# Bank1_I_O.net
KiCad netlist of a schematic drawn in Altium Designer
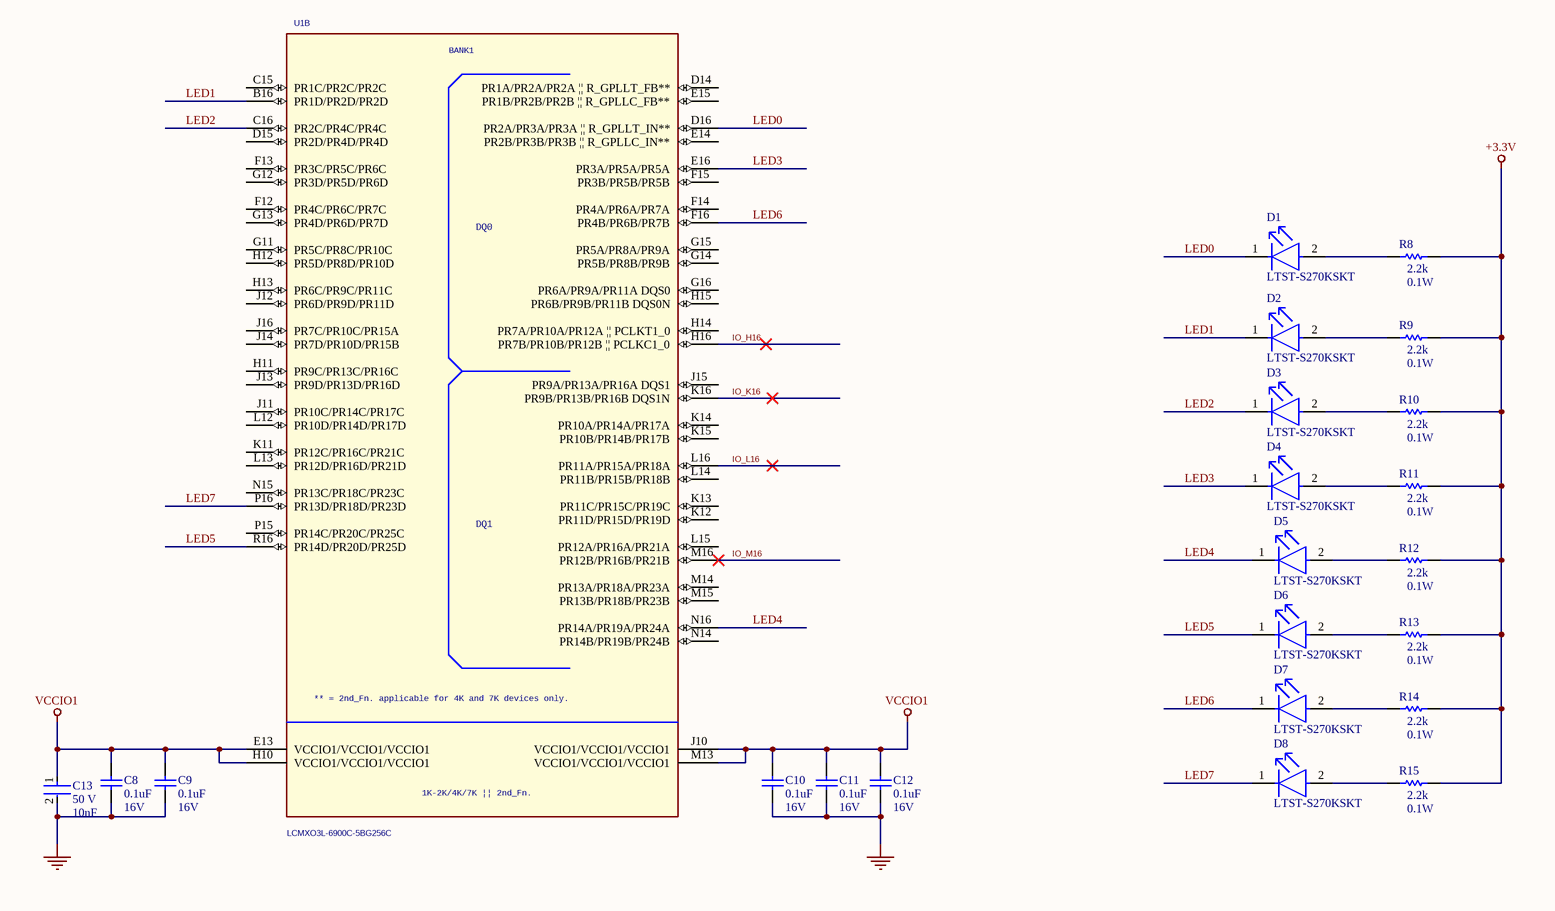
[diagram p0: Bank1_I_O.SchDoc]

(export (version "E")
  (design (tool "Eeschema 10.0.6"))
  (components
    (comp (ref "C8")
      (value "0.1uF")
      (footprint "CAPC1608X87X35ML15T15")
      (description "Ceramic Capacitor 0.1uF 16V +-10% X7R0603")
      (fields
        (field (name "PART NUMBER") "C0603C104M4RACTU")
        (field (name "MANUFACTURER") "Kemet")
        (field (name "VOLTAGE") "16V")
      )
      (libsource (lib "Altium Content Vault") (part "CAP"))
    )
    (comp (ref "C9")
      (value "0.1uF")
      (footprint "CAPC1608X87X35ML15T15")
      (description "Ceramic Capacitor 0.1uF 16V +-10% X7R0603")
      (fields
        (field (name "PART NUMBER") "C0603C104M4RACTU")
        (field (name "MANUFACTURER") "Kemet")
        (field (name "VOLTAGE") "16V")
      )
      (libsource (lib "Altium Content Vault") (part "CAP"))
    )
    (comp (ref "C10")
      (value "0.1uF")
      (footprint "CAPC1608X87X35ML15T15")
      (description "Ceramic Capacitor 0.1uF 16V +-10% X7R0603")
      (fields
        (field (name "PART NUMBER") "C0603C104M4RACTU")
        (field (name "MANUFACTURER") "Kemet")
        (field (name "VOLTAGE") "16V")
      )
      (libsource (lib "Altium Content Vault") (part "CAP"))
    )
    (comp (ref "C11")
      (value "0.1uF")
      (footprint "CAPC1608X87X35ML15T15")
      (description "Ceramic Capacitor 0.1uF 16V +-10% X7R0603")
      (fields
        (field (name "PART NUMBER") "C0603C104M4RACTU")
        (field (name "MANUFACTURER") "Kemet")
        (field (name "VOLTAGE") "16V")
      )
      (libsource (lib "Altium Content Vault") (part "CAP"))
    )
    (comp (ref "C12")
      (value "0.1uF")
      (footprint "CAPC1608X87X35ML15T15")
      (description "Ceramic Capacitor 0.1uF 16V +-10% X7R0603")
      (fields
        (field (name "PART NUMBER") "C0603C104M4RACTU")
        (field (name "MANUFACTURER") "Kemet")
        (field (name "VOLTAGE") "16V")
      )
      (libsource (lib "Altium Content Vault") (part "CAP"))
    )
    (comp (ref "C13")
      (value "10nF")
      (footprint "FP-C0805C-DN-MFG")
      (description "CAP CER 10000PF 50V X7R 0805")
      (fields
        (field (name "VOLTAGE") "50 V")
        (field (name "PART NUMBER") "C0805C103K5RACAUTO")
        (field (name "MANUFACTURER") "KEMET")
      )
      (libsource (lib "Altium Content Vault") (part "b4654b650e69147ec39a6b967a45e02"))
    )
    (comp (ref "D1")
      (value "LTST-S270KSKT")
      (footprint "FP-LTST-S270KSKT-MFG")
      (description "LED YELLOW CLEAR CHIP SMD R/A")
      (libsource (lib "Altium Content Vault") (part "8706943c75ba83719d021d2fdc84c58"))
    )
    (comp (ref "D2")
      (value "LTST-S270KSKT")
      (footprint "FP-LTST-S270KSKT-MFG")
      (description "LED YELLOW CLEAR CHIP SMD R/A")
      (libsource (lib "Altium Content Vault") (part "8706943c75ba83719d021d2fdc84c58"))
    )
    (comp (ref "D3")
      (value "LTST-S270KSKT")
      (footprint "FP-LTST-S270KSKT-MFG")
      (description "LED YELLOW CLEAR CHIP SMD R/A")
      (libsource (lib "Altium Content Vault") (part "8706943c75ba83719d021d2fdc84c58"))
    )
    (comp (ref "D4")
      (value "LTST-S270KSKT")
      (footprint "FP-LTST-S270KSKT-MFG")
      (description "LED YELLOW CLEAR CHIP SMD R/A")
      (libsource (lib "Altium Content Vault") (part "8706943c75ba83719d021d2fdc84c58"))
    )
    (comp (ref "D5")
      (value "LTST-S270KSKT")
      (footprint "FP-LTST-S270KSKT-MFG")
      (description "LED YELLOW CLEAR CHIP SMD R/A")
      (libsource (lib "Altium Content Vault") (part "8706943c75ba83719d021d2fdc84c58"))
    )
    (comp (ref "D6")
      (value "LTST-S270KSKT")
      (footprint "FP-LTST-S270KSKT-MFG")
      (description "LED YELLOW CLEAR CHIP SMD R/A")
      (libsource (lib "Altium Content Vault") (part "8706943c75ba83719d021d2fdc84c58"))
    )
    (comp (ref "D7")
      (value "LTST-S270KSKT")
      (footprint "FP-LTST-S270KSKT-MFG")
      (description "LED YELLOW CLEAR CHIP SMD R/A")
      (libsource (lib "Altium Content Vault") (part "8706943c75ba83719d021d2fdc84c58"))
    )
    (comp (ref "D8")
      (value "LTST-S270KSKT")
      (footprint "FP-LTST-S270KSKT-MFG")
      (description "LED YELLOW CLEAR CHIP SMD R/A")
      (libsource (lib "Altium Content Vault") (part "8706943c75ba83719d021d2fdc84c58"))
    )
    (comp (ref "R8")
      (value "2.2k")
      (footprint "RESC1608X55X25LL10T15")
      (fields
        (field (name "TOLERANCE") "1%")
        (field (name "VOLTAGE") "50V")
        (field (name "MANUFACTURER") "Yageo")
        (field (name "POWER") "0.1W")
      )
      (libsource (lib "Altium Content Vault") (part "RES-2"))
    )
    (comp (ref "R9")
      (value "2.2k")
      (footprint "RESC1608X55X25LL10T15")
      (fields
        (field (name "TOLERANCE") "1%")
        (field (name "VOLTAGE") "50V")
        (field (name "MANUFACTURER") "Yageo")
        (field (name "POWER") "0.1W")
      )
      (libsource (lib "Altium Content Vault") (part "RES-2"))
    )
    (comp (ref "R10")
      (value "2.2k")
      (footprint "RESC1608X55X25LL10T15")
      (fields
        (field (name "TOLERANCE") "1%")
        (field (name "VOLTAGE") "50V")
        (field (name "MANUFACTURER") "Yageo")
        (field (name "POWER") "0.1W")
      )
      (libsource (lib "Altium Content Vault") (part "RES-2"))
    )
    (comp (ref "R11")
      (value "2.2k")
      (footprint "RESC1608X55X25LL10T15")
      (fields
        (field (name "TOLERANCE") "1%")
        (field (name "VOLTAGE") "50V")
        (field (name "MANUFACTURER") "Yageo")
        (field (name "POWER") "0.1W")
      )
      (libsource (lib "Altium Content Vault") (part "RES-2"))
    )
    (comp (ref "R12")
      (value "2.2k")
      (footprint "RESC1608X55X25LL10T15")
      (fields
        (field (name "TOLERANCE") "1%")
        (field (name "VOLTAGE") "50V")
        (field (name "MANUFACTURER") "Yageo")
        (field (name "POWER") "0.1W")
      )
      (libsource (lib "Altium Content Vault") (part "RES-2"))
    )
    (comp (ref "R13")
      (value "2.2k")
      (footprint "RESC1608X55X25LL10T15")
      (fields
        (field (name "TOLERANCE") "1%")
        (field (name "VOLTAGE") "50V")
        (field (name "MANUFACTURER") "Yageo")
        (field (name "POWER") "0.1W")
      )
      (libsource (lib "Altium Content Vault") (part "RES-2"))
    )
    (comp (ref "R14")
      (value "2.2k")
      (footprint "RESC1608X55X25LL10T15")
      (fields
        (field (name "TOLERANCE") "1%")
        (field (name "VOLTAGE") "50V")
        (field (name "MANUFACTURER") "Yageo")
        (field (name "POWER") "0.1W")
      )
      (libsource (lib "Altium Content Vault") (part "RES-2"))
    )
    (comp (ref "R15")
      (value "2.2k")
      (footprint "RESC1608X55X25LL10T15")
      (fields
        (field (name "TOLERANCE") "1%")
        (field (name "VOLTAGE") "50V")
        (field (name "MANUFACTURER") "Yageo")
        (field (name "POWER") "0.1W")
      )
      (libsource (lib "Altium Content Vault") (part "RES-2"))
    )
    (comp (ref "U1")
      (value "LCMXO3L-6900C-5BG256C")
      (footprint "BGA256C80P16X16_1400X1400X170")
      (description "IC FPGA 6864LUTS 256BGA")
      (fields (field (name "MANUFACTURER") "Lattice semi"))
      (libsource (lib "*") (part "LCMXO3L-1K/2K/4K/7K-BG256"))
    )
  )
  (nets
    (net (code "1") (name "+3.3V") (class "Default")
      (node (ref "R10") (pin "2") (pinfunction "2_2") (pintype "passive"))
      (node (ref "R11") (pin "2") (pinfunction "2_2") (pintype "passive"))
      (node (ref "R12") (pin "2") (pinfunction "2_2") (pintype "passive"))
      (node (ref "R13") (pin "2") (pinfunction "2_2") (pintype "passive"))
      (node (ref "R14") (pin "2") (pinfunction "2_2") (pintype "passive"))
      (node (ref "R15") (pin "2") (pinfunction "2_2") (pintype "passive"))
      (node (ref "R8") (pin "2") (pinfunction "2_2") (pintype "passive"))
      (node (ref "R9") (pin "2") (pinfunction "2_2") (pintype "passive"))
    )
    (net (code "2") (name "/IO_H16") (class "Default")
      (node (ref "U1") (pin "H16") (pinfunction "PR7B/PR10B/PR12B_Ζ_PCLKC1_0_H16") (pintype "bidirectional"))
    )
    (net (code "3") (name "/IO_K16") (class "Default")
      (node (ref "U1") (pin "K16") (pinfunction "PR9B/PR13B/PR16B_DQS1N_K16") (pintype "bidirectional"))
    )
    (net (code "4") (name "/IO_L16") (class "Default")
      (node (ref "U1") (pin "L16") (pinfunction "PR11A/PR15A/PR18A_L16") (pintype "bidirectional"))
    )
    (net (code "5") (name "/IO_M16") (class "Default")
      (node (ref "U1") (pin "M16") (pinfunction "PR12B/PR16B/PR21B_M16") (pintype "bidirectional+no_connect"))
    )
    (net (code "6") (name "/LED0") (class "Default")
      (node (ref "D1") (pin "1") (pinfunction "C_1") (pintype "passive"))
      (node (ref "U1") (pin "D16") (pinfunction "PR2A/PR3A/PR3A_Ζ_R_GPLLT_IN**_D16") (pintype "bidirectional"))
    )
    (net (code "7") (name "/LED1") (class "Default")
      (node (ref "D2") (pin "1") (pinfunction "C_1") (pintype "passive"))
      (node (ref "U1") (pin "B16") (pinfunction "PR1D/PR2D/PR2D_B16") (pintype "bidirectional"))
    )
    (net (code "8") (name "/LED2") (class "Default")
      (node (ref "D3") (pin "1") (pinfunction "C_1") (pintype "passive"))
      (node (ref "U1") (pin "C16") (pinfunction "PR2C/PR4C/PR4C_C16") (pintype "bidirectional"))
    )
    (net (code "9") (name "/LED3") (class "Default")
      (node (ref "D4") (pin "1") (pinfunction "C_1") (pintype "passive"))
      (node (ref "U1") (pin "E16") (pinfunction "PR3A/PR5A/PR5A_E16") (pintype "bidirectional"))
    )
    (net (code "10") (name "/LED4") (class "Default")
      (node (ref "D5") (pin "1") (pinfunction "C_1") (pintype "passive"))
      (node (ref "U1") (pin "N16") (pinfunction "PR14A/PR19A/PR24A_N16") (pintype "bidirectional"))
    )
    (net (code "11") (name "/LED5") (class "Default")
      (node (ref "D6") (pin "1") (pinfunction "C_1") (pintype "passive"))
      (node (ref "U1") (pin "R16") (pinfunction "PR14D/PR20D/PR25D_R16") (pintype "bidirectional"))
    )
    (net (code "12") (name "/LED6") (class "Default")
      (node (ref "D7") (pin "1") (pinfunction "C_1") (pintype "passive"))
      (node (ref "U1") (pin "F16") (pinfunction "PR4B/PR6B/PR7B_F16") (pintype "bidirectional"))
    )
    (net (code "13") (name "/LED7") (class "Default")
      (node (ref "D8") (pin "1") (pinfunction "C_1") (pintype "passive"))
      (node (ref "U1") (pin "P16") (pinfunction "PR13D/PR18D/PR23D_P16") (pintype "bidirectional"))
    )
    (net (code "14") (name "GND") (class "Default")
      (node (ref "C10") (pin "2") (pinfunction "2_2") (pintype "passive"))
      (node (ref "C11") (pin "2") (pinfunction "2_2") (pintype "passive"))
      (node (ref "C12") (pin "2") (pinfunction "2_2") (pintype "passive"))
      (node (ref "C13") (pin "2") (pinfunction "2_2") (pintype "passive"))
      (node (ref "C8") (pin "2") (pinfunction "2_2") (pintype "passive"))
      (node (ref "C9") (pin "2") (pinfunction "2_2") (pintype "passive"))
    )
    (net (code "15") (name "Net-(D1-A)") (class "Default")
      (node (ref "D1") (pin "2") (pinfunction "A_2") (pintype "passive"))
      (node (ref "R8") (pin "1") (pinfunction "1_1") (pintype "passive"))
    )
    (net (code "16") (name "Net-(D2-A)") (class "Default")
      (node (ref "D2") (pin "2") (pinfunction "A_2") (pintype "passive"))
      (node (ref "R9") (pin "1") (pinfunction "1_1") (pintype "passive"))
    )
    (net (code "17") (name "Net-(D3-A)") (class "Default")
      (node (ref "D3") (pin "2") (pinfunction "A_2") (pintype "passive"))
      (node (ref "R10") (pin "1") (pinfunction "1_1") (pintype "passive"))
    )
    (net (code "18") (name "Net-(D4-A)") (class "Default")
      (node (ref "D4") (pin "2") (pinfunction "A_2") (pintype "passive"))
      (node (ref "R11") (pin "1") (pinfunction "1_1") (pintype "passive"))
    )
    (net (code "19") (name "Net-(D5-A)") (class "Default")
      (node (ref "D5") (pin "2") (pinfunction "A_2") (pintype "passive"))
      (node (ref "R12") (pin "1") (pinfunction "1_1") (pintype "passive"))
    )
    (net (code "20") (name "Net-(D6-A)") (class "Default")
      (node (ref "D6") (pin "2") (pinfunction "A_2") (pintype "passive"))
      (node (ref "R13") (pin "1") (pinfunction "1_1") (pintype "passive"))
    )
    (net (code "21") (name "Net-(D7-A)") (class "Default")
      (node (ref "D7") (pin "2") (pinfunction "A_2") (pintype "passive"))
      (node (ref "R14") (pin "1") (pinfunction "1_1") (pintype "passive"))
    )
    (net (code "22") (name "Net-(D8-A)") (class "Default")
      (node (ref "D8") (pin "2") (pinfunction "A_2") (pintype "passive"))
      (node (ref "R15") (pin "1") (pinfunction "1_1") (pintype "passive"))
    )
    (net (code "23") (name "VCCIO1") (class "Default")
      (node (ref "C10") (pin "1") (pinfunction "1_1") (pintype "passive"))
      (node (ref "C11") (pin "1") (pinfunction "1_1") (pintype "passive"))
      (node (ref "C12") (pin "1") (pinfunction "1_1") (pintype "passive"))
      (node (ref "C13") (pin "1") (pinfunction "1_1") (pintype "passive"))
      (node (ref "C8") (pin "1") (pinfunction "1_1") (pintype "passive"))
      (node (ref "C9") (pin "1") (pinfunction "1_1") (pintype "passive"))
      (node (ref "U1") (pin "E13") (pinfunction "VCCIO1/VCCIO1/VCCIO1_E13") (pintype "power_in"))
      (node (ref "U1") (pin "H10") (pinfunction "VCCIO1/VCCIO1/VCCIO1_H10") (pintype "power_in"))
      (node (ref "U1") (pin "J10") (pinfunction "VCCIO1/VCCIO1/VCCIO1_J10") (pintype "power_in"))
      (node (ref "U1") (pin "M13") (pinfunction "VCCIO1/VCCIO1/VCCIO1_M13") (pintype "power_in"))
    )
    (net (code "24") (name "unconnected-(U1B-PR1A{slash}PR2A{slash}PR2A_Ζ_R_GPLLT_FB**-PadD14)") (class "Default")
      (node (ref "U1") (pin "D14") (pinfunction "PR1A/PR2A/PR2A_Ζ_R_GPLLT_FB**_D14") (pintype "bidirectional"))
    )
    (net (code "25") (name "unconnected-(U1B-PR1B{slash}PR2B{slash}PR2B_Ζ_R_GPLLC_FB**-PadE15)") (class "Default")
      (node (ref "U1") (pin "E15") (pinfunction "PR1B/PR2B/PR2B_Ζ_R_GPLLC_FB**_E15") (pintype "bidirectional"))
    )
    (net (code "26") (name "unconnected-(U1B-PR1C{slash}PR2C{slash}PR2C-PadC15)") (class "Default")
      (node (ref "U1") (pin "C15") (pinfunction "PR1C/PR2C/PR2C_C15") (pintype "bidirectional"))
    )
    (net (code "27") (name "unconnected-(U1B-PR2B{slash}PR3B{slash}PR3B_Ζ_R_GPLLC_IN**-PadE14)") (class "Default")
      (node (ref "U1") (pin "E14") (pinfunction "PR2B/PR3B/PR3B_Ζ_R_GPLLC_IN**_E14") (pintype "bidirectional"))
    )
    (net (code "28") (name "unconnected-(U1B-PR2D{slash}PR4D{slash}PR4D-PadD15)") (class "Default")
      (node (ref "U1") (pin "D15") (pinfunction "PR2D/PR4D/PR4D_D15") (pintype "bidirectional"))
    )
    (net (code "29") (name "unconnected-(U1B-PR3B{slash}PR5B{slash}PR5B-PadF15)") (class "Default")
      (node (ref "U1") (pin "F15") (pinfunction "PR3B/PR5B/PR5B_F15") (pintype "bidirectional"))
    )
    (net (code "30") (name "unconnected-(U1B-PR3C{slash}PR5C{slash}PR6C-PadF13)") (class "Default")
      (node (ref "U1") (pin "F13") (pinfunction "PR3C/PR5C/PR6C_F13") (pintype "bidirectional"))
    )
    (net (code "31") (name "unconnected-(U1B-PR3D{slash}PR5D{slash}PR6D-PadG12)") (class "Default")
      (node (ref "U1") (pin "G12") (pinfunction "PR3D/PR5D/PR6D_G12") (pintype "bidirectional"))
    )
    (net (code "32") (name "unconnected-(U1B-PR4A{slash}PR6A{slash}PR7A-PadF14)") (class "Default")
      (node (ref "U1") (pin "F14") (pinfunction "PR4A/PR6A/PR7A_F14") (pintype "bidirectional"))
    )
    (net (code "33") (name "unconnected-(U1B-PR4C{slash}PR6C{slash}PR7C-PadF12)") (class "Default")
      (node (ref "U1") (pin "F12") (pinfunction "PR4C/PR6C/PR7C_F12") (pintype "bidirectional"))
    )
    (net (code "34") (name "unconnected-(U1B-PR4D{slash}PR6D{slash}PR7D-PadG13)") (class "Default")
      (node (ref "U1") (pin "G13") (pinfunction "PR4D/PR6D/PR7D_G13") (pintype "bidirectional"))
    )
    (net (code "35") (name "unconnected-(U1B-PR5A{slash}PR8A{slash}PR9A-PadG15)") (class "Default")
      (node (ref "U1") (pin "G15") (pinfunction "PR5A/PR8A/PR9A_G15") (pintype "bidirectional"))
    )
    (net (code "36") (name "unconnected-(U1B-PR5B{slash}PR8B{slash}PR9B-PadG14)") (class "Default")
      (node (ref "U1") (pin "G14") (pinfunction "PR5B/PR8B/PR9B_G14") (pintype "bidirectional"))
    )
    (net (code "37") (name "unconnected-(U1B-PR5C{slash}PR8C{slash}PR10C-PadG11)") (class "Default")
      (node (ref "U1") (pin "G11") (pinfunction "PR5C/PR8C/PR10C_G11") (pintype "bidirectional"))
    )
    (net (code "38") (name "unconnected-(U1B-PR5D{slash}PR8D{slash}PR10D-PadH12)") (class "Default")
      (node (ref "U1") (pin "H12") (pinfunction "PR5D/PR8D/PR10D_H12") (pintype "bidirectional"))
    )
    (net (code "39") (name "unconnected-(U1B-PR6A{slash}PR9A{slash}PR11A_DQS0-PadG16)") (class "Default")
      (node (ref "U1") (pin "G16") (pinfunction "PR6A/PR9A/PR11A_DQS0_G16") (pintype "bidirectional"))
    )
    (net (code "40") (name "unconnected-(U1B-PR6B{slash}PR9B{slash}PR11B_DQS0N-PadH15)") (class "Default")
      (node (ref "U1") (pin "H15") (pinfunction "PR6B/PR9B/PR11B_DQS0N_H15") (pintype "bidirectional"))
    )
    (net (code "41") (name "unconnected-(U1B-PR6C{slash}PR9C{slash}PR11C-PadH13)") (class "Default")
      (node (ref "U1") (pin "H13") (pinfunction "PR6C/PR9C/PR11C_H13") (pintype "bidirectional"))
    )
    (net (code "42") (name "unconnected-(U1B-PR6D{slash}PR9D{slash}PR11D-PadJ12)") (class "Default")
      (node (ref "U1") (pin "J12") (pinfunction "PR6D/PR9D/PR11D_J12") (pintype "bidirectional"))
    )
    (net (code "43") (name "unconnected-(U1B-PR7A{slash}PR10A{slash}PR12A_Ζ_PCLKT1_0-PadH14)") (class "Default")
      (node (ref "U1") (pin "H14") (pinfunction "PR7A/PR10A/PR12A_Ζ_PCLKT1_0_H14") (pintype "bidirectional"))
    )
    (net (code "44") (name "unconnected-(U1B-PR7C{slash}PR10C{slash}PR15A-PadJ16)") (class "Default")
      (node (ref "U1") (pin "J16") (pinfunction "PR7C/PR10C/PR15A_J16") (pintype "bidirectional"))
    )
    (net (code "45") (name "unconnected-(U1B-PR7D{slash}PR10D{slash}PR15B-PadJ14)") (class "Default")
      (node (ref "U1") (pin "J14") (pinfunction "PR7D/PR10D/PR15B_J14") (pintype "bidirectional"))
    )
    (net (code "46") (name "unconnected-(U1B-PR9A{slash}PR13A{slash}PR16A_DQS1-PadJ15)") (class "Default")
      (node (ref "U1") (pin "J15") (pinfunction "PR9A/PR13A/PR16A_DQS1_J15") (pintype "bidirectional"))
    )
    (net (code "47") (name "unconnected-(U1B-PR9C{slash}PR13C{slash}PR16C-PadH11)") (class "Default")
      (node (ref "U1") (pin "H11") (pinfunction "PR9C/PR13C/PR16C_H11") (pintype "bidirectional"))
    )
    (net (code "48") (name "unconnected-(U1B-PR9D{slash}PR13D{slash}PR16D-PadJ13)") (class "Default")
      (node (ref "U1") (pin "J13") (pinfunction "PR9D/PR13D/PR16D_J13") (pintype "bidirectional"))
    )
    (net (code "49") (name "unconnected-(U1B-PR10A{slash}PR14A{slash}PR17A-PadK14)") (class "Default")
      (node (ref "U1") (pin "K14") (pinfunction "PR10A/PR14A/PR17A_K14") (pintype "bidirectional"))
    )
    (net (code "50") (name "unconnected-(U1B-PR10B{slash}PR14B{slash}PR17B-PadK15)") (class "Default")
      (node (ref "U1") (pin "K15") (pinfunction "PR10B/PR14B/PR17B_K15") (pintype "bidirectional"))
    )
    (net (code "51") (name "unconnected-(U1B-PR10C{slash}PR14C{slash}PR17C-PadJ11)") (class "Default")
      (node (ref "U1") (pin "J11") (pinfunction "PR10C/PR14C/PR17C_J11") (pintype "bidirectional"))
    )
    (net (code "52") (name "unconnected-(U1B-PR10D{slash}PR14D{slash}PR17D-PadL12)") (class "Default")
      (node (ref "U1") (pin "L12") (pinfunction "PR10D/PR14D/PR17D_L12") (pintype "bidirectional"))
    )
    (net (code "53") (name "unconnected-(U1B-PR11B{slash}PR15B{slash}PR18B-PadL14)") (class "Default")
      (node (ref "U1") (pin "L14") (pinfunction "PR11B/PR15B/PR18B_L14") (pintype "bidirectional"))
    )
    (net (code "54") (name "unconnected-(U1B-PR11C{slash}PR15C{slash}PR19C-PadK13)") (class "Default")
      (node (ref "U1") (pin "K13") (pinfunction "PR11C/PR15C/PR19C_K13") (pintype "bidirectional"))
    )
    (net (code "55") (name "unconnected-(U1B-PR11D{slash}PR15D{slash}PR19D-PadK12)") (class "Default")
      (node (ref "U1") (pin "K12") (pinfunction "PR11D/PR15D/PR19D_K12") (pintype "bidirectional"))
    )
    (net (code "56") (name "unconnected-(U1B-PR12A{slash}PR16A{slash}PR21A-PadL15)") (class "Default")
      (node (ref "U1") (pin "L15") (pinfunction "PR12A/PR16A/PR21A_L15") (pintype "bidirectional"))
    )
    (net (code "57") (name "unconnected-(U1B-PR12C{slash}PR16C{slash}PR21C-PadK11)") (class "Default")
      (node (ref "U1") (pin "K11") (pinfunction "PR12C/PR16C/PR21C_K11") (pintype "bidirectional"))
    )
    (net (code "58") (name "unconnected-(U1B-PR12D{slash}PR16D{slash}PR21D-PadL13)") (class "Default")
      (node (ref "U1") (pin "L13") (pinfunction "PR12D/PR16D/PR21D_L13") (pintype "bidirectional"))
    )
    (net (code "59") (name "unconnected-(U1B-PR13A{slash}PR18A{slash}PR23A-PadM14)") (class "Default")
      (node (ref "U1") (pin "M14") (pinfunction "PR13A/PR18A/PR23A_M14") (pintype "bidirectional"))
    )
    (net (code "60") (name "unconnected-(U1B-PR13B{slash}PR18B{slash}PR23B-PadM15)") (class "Default")
      (node (ref "U1") (pin "M15") (pinfunction "PR13B/PR18B/PR23B_M15") (pintype "bidirectional"))
    )
    (net (code "61") (name "unconnected-(U1B-PR13C{slash}PR18C{slash}PR23C-PadN15)") (class "Default")
      (node (ref "U1") (pin "N15") (pinfunction "PR13C/PR18C/PR23C_N15") (pintype "bidirectional"))
    )
    (net (code "62") (name "unconnected-(U1B-PR14B{slash}PR19B{slash}PR24B-PadN14)") (class "Default")
      (node (ref "U1") (pin "N14") (pinfunction "PR14B/PR19B/PR24B_N14") (pintype "bidirectional"))
    )
    (net (code "63") (name "unconnected-(U1B-PR14C{slash}PR20C{slash}PR25C-PadP15)") (class "Default")
      (node (ref "U1") (pin "P15") (pinfunction "PR14C/PR20C/PR25C_P15") (pintype "bidirectional"))
    )
  )
)
